# SilentStepStick-TMC2130_v10.net
KiCad netlist of a schematic drawn in EAGLE
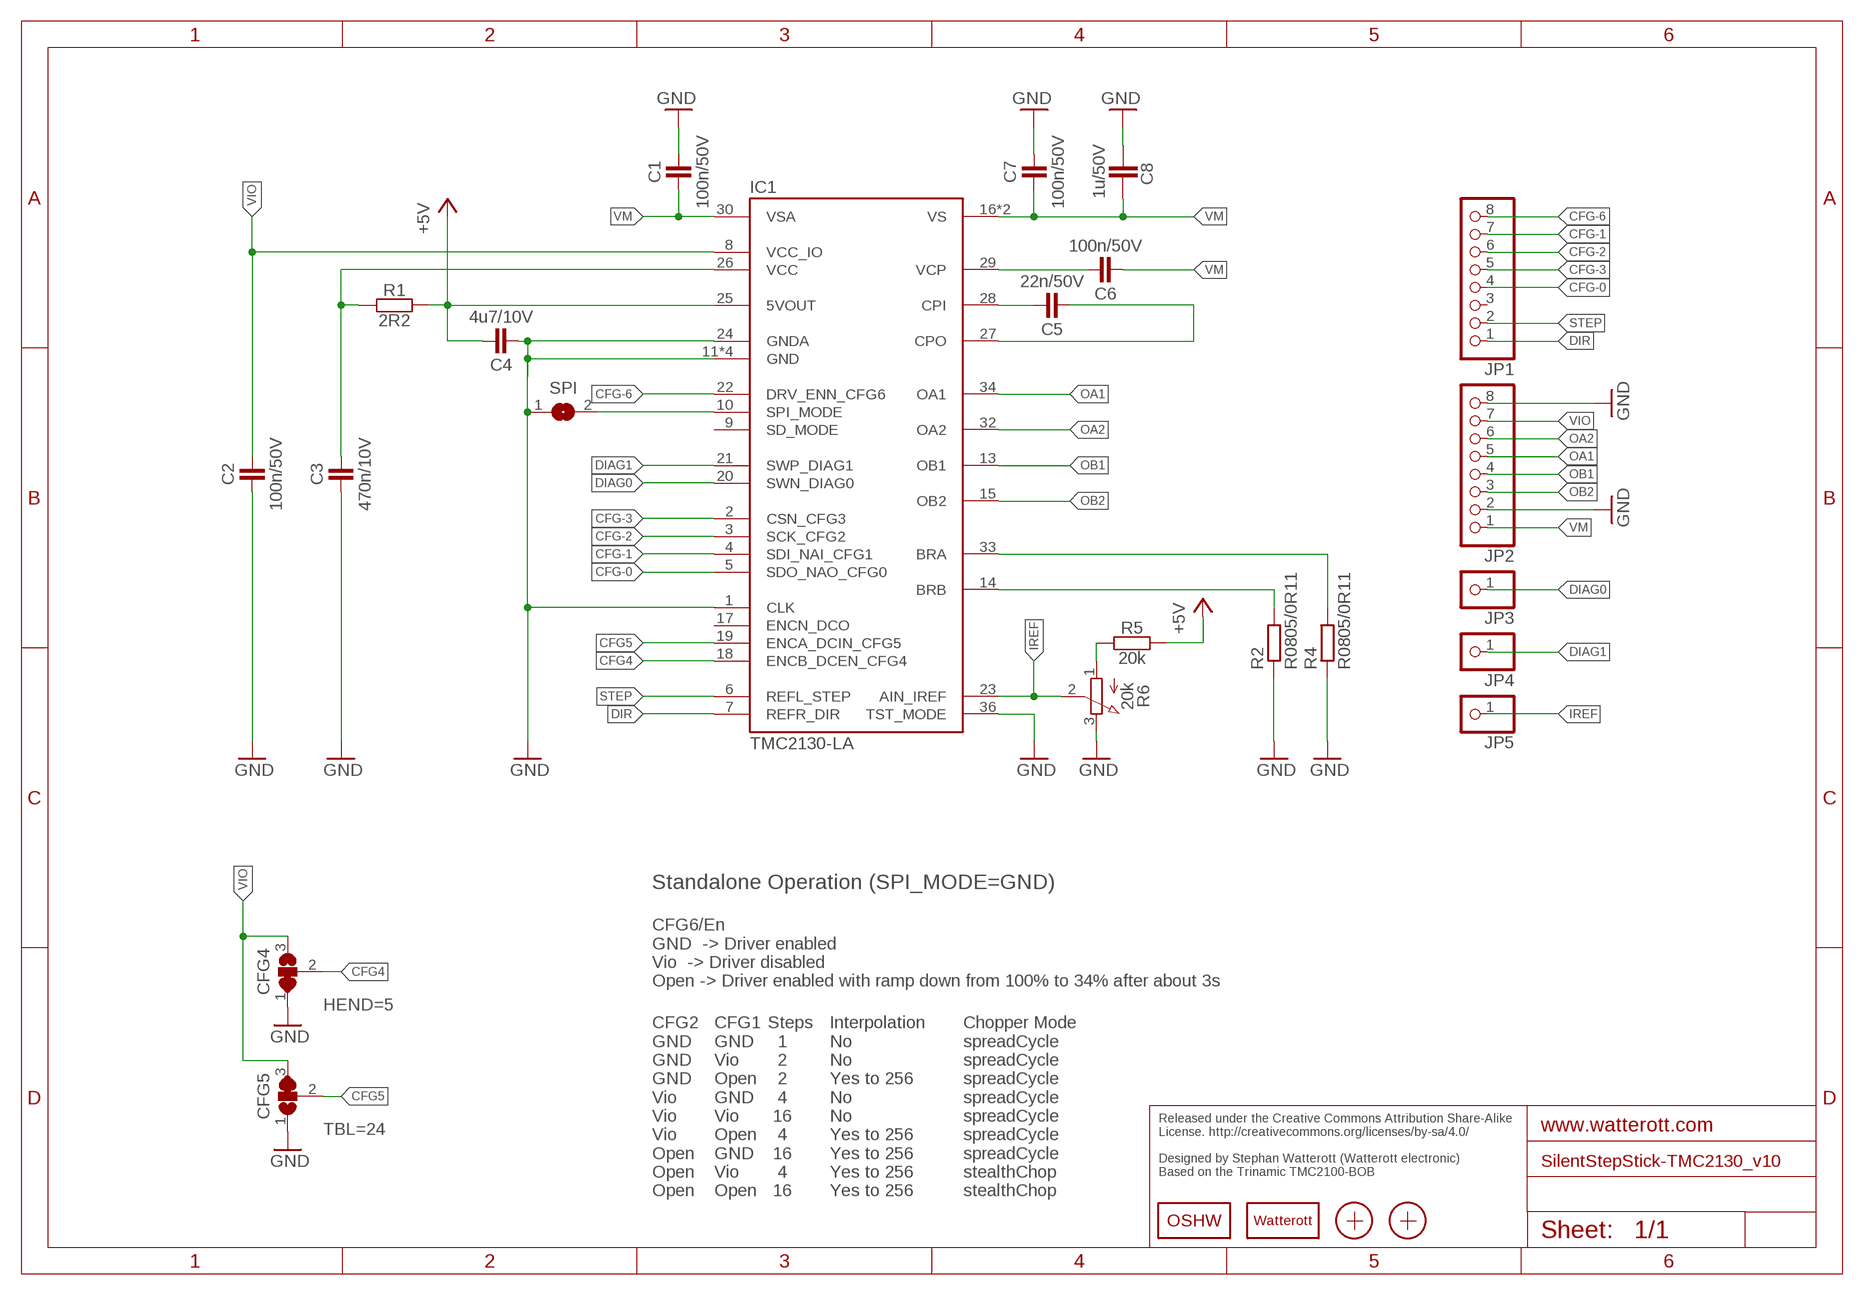
[diagram p0: schematic, sheet 1]

(export (version "E")
  (design (tool "Eeschema 10.0.6"))
  (components
    (comp (ref "C1")
      (value "100n/50V")
      (footprint "eagle-import:C0402")
      (libsource (lib "eagle-import") (part "CAPACITOR-0402"))
    )
    (comp (ref "C2")
      (value "100n/50V")
      (footprint "eagle-import:C0402")
      (libsource (lib "eagle-import") (part "CAPACITOR-0402"))
    )
    (comp (ref "C3")
      (value "470n/10V")
      (footprint "eagle-import:C0402")
      (libsource (lib "eagle-import") (part "CAPACITOR-0402"))
    )
    (comp (ref "C4")
      (value "4u7/10V")
      (footprint "eagle-import:C0402")
      (libsource (lib "eagle-import") (part "CAPACITOR-0402"))
    )
    (comp (ref "C5")
      (value "22n/50V")
      (footprint "eagle-import:C0402")
      (libsource (lib "eagle-import") (part "CAPACITOR-0402"))
    )
    (comp (ref "C6")
      (value "100n/50V")
      (footprint "eagle-import:C0402")
      (libsource (lib "eagle-import") (part "CAPACITOR-0402"))
    )
    (comp (ref "C7")
      (value "100n/50V")
      (footprint "eagle-import:C0402")
      (libsource (lib "eagle-import") (part "CAPACITOR-0402"))
    )
    (comp (ref "C8")
      (value "1u/50V")
      (footprint "eagle-import:C0603")
      (libsource (lib "eagle-import") (part "C-EUC0603"))
    )
    (comp (ref "CFG4")
      (value "JUMPER3-0201")
      (footprint "eagle-import:JUMPER3-0201")
      (libsource (lib "eagle-import") (part "JUMPER3-0201"))
    )
    (comp (ref "CFG5")
      (value "JUMPER3-0201")
      (footprint "eagle-import:JUMPER3-0201")
      (libsource (lib "eagle-import") (part "JUMPER3-0201"))
    )
    (comp (ref "IC1")
      (value "TMC2130-LA")
      (footprint "eagle-import:QFN36-PAD")
      (libsource (lib "eagle-import") (part "TMC21X0-LA"))
    )
    (comp (ref "JP1")
      (value "PINHD-1X08_2.54-S")
      (footprint "eagle-import:1X08-S")
      (libsource (lib "eagle-import") (part "PINHD-1X08_2.54-S"))
    )
    (comp (ref "JP2")
      (value "PINHD-1X08_2.54-S")
      (footprint "eagle-import:1X08-S")
      (libsource (lib "eagle-import") (part "PINHD-1X08_2.54-S"))
    )
    (comp (ref "JP3")
      (value "PINHD-1X1")
      (footprint "eagle-import:1X01")
      (libsource (lib "eagle-import") (part "PINHD-1X1"))
    )
    (comp (ref "JP4")
      (value "PINHD-1X1")
      (footprint "eagle-import:1X01")
      (libsource (lib "eagle-import") (part "PINHD-1X1"))
    )
    (comp (ref "JP5")
      (value "PINHD-1X1")
      (footprint "eagle-import:1X01")
      (libsource (lib "eagle-import") (part "PINHD-1X1"))
    )
    (comp (ref "LOGO1")
      (value "OSHW_LOGOX0070")
      (footprint "eagle-import:OSHW_6X70")
      (libsource (lib "eagle-import") (part "OSHW_LOGOX0070"))
    )
    (comp (ref "LOGO2")
      (value "LOGO-S_PLACE_M")
      (footprint "eagle-import:SPARK_TPLACE_M")
      (libsource (lib "eagle-import") (part "LOGO-S_PLACE_M"))
    )
    (comp (ref "R1")
      (value "2R2")
      (footprint "eagle-import:C0402")
      (libsource (lib "eagle-import") (part "RESISTOR-0402"))
    )
    (comp (ref "R2")
      (value "R0805/0R11")
      (footprint "eagle-import:M0805")
      (libsource (lib "eagle-import") (part "R-EU_M0805"))
    )
    (comp (ref "R4")
      (value "R0805/0R11")
      (footprint "eagle-import:M0805")
      (libsource (lib "eagle-import") (part "R-EU_M0805"))
    )
    (comp (ref "R5")
      (value "20k")
      (footprint "eagle-import:C0402")
      (libsource (lib "eagle-import") (part "RESISTOR-0402"))
    )
    (comp (ref "R6")
      (value "20k")
      (footprint "eagle-import:POT_EVM3R")
      (libsource (lib "eagle-import") (part "POTEVM3R"))
    )
    (comp (ref "SPI")
      (value "JUMPER2-0402-NC")
      (footprint "eagle-import:JUMPER2-0402_NC")
      (libsource (lib "eagle-import") (part "JUMPER2-0402-NC"))
    )
    (comp (ref "X1")
      (value "PASSER-07")
      (footprint "eagle-import:PASSER_07MM")
      (libsource (lib "eagle-import") (part "PASSER-07"))
    )
    (comp (ref "X2")
      (value "PASSER-07")
      (footprint "eagle-import:PASSER_07MM")
      (libsource (lib "eagle-import") (part "PASSER-07"))
    )
  )
  (nets
    (net (code "1") (name "+5V") (class "Default")
      (node (ref "C4") (pin "2") (pinfunction "2_2") (pintype "passive"))
      (node (ref "IC1") (pin "25") (pinfunction "5VOUT_25") (pintype "power_in"))
      (node (ref "R1") (pin "2") (pinfunction "2_2") (pintype "passive"))
      (node (ref "R5") (pin "2") (pinfunction "2_2") (pintype "passive"))
    )
    (net (code "2") (name "CFG-0") (class "Default")
      (node (ref "IC1") (pin "5") (pinfunction "SDO_NAO_CFG0_5") (pintype "bidirectional"))
      (node (ref "JP1") (pin "4") (pinfunction "4_4") (pintype "passive"))
    )
    (net (code "3") (name "CFG-1") (class "Default")
      (node (ref "IC1") (pin "4") (pinfunction "SDI_NAI_CFG1_4") (pintype "bidirectional"))
      (node (ref "JP1") (pin "7") (pinfunction "7_7") (pintype "passive"))
    )
    (net (code "4") (name "CFG-2") (class "Default")
      (node (ref "IC1") (pin "3") (pinfunction "SCK_CFG2_3") (pintype "bidirectional"))
      (node (ref "JP1") (pin "6") (pinfunction "6_6") (pintype "passive"))
    )
    (net (code "5") (name "CFG-3") (class "Default")
      (node (ref "IC1") (pin "2") (pinfunction "CSN_CFG3_2") (pintype "bidirectional"))
      (node (ref "JP1") (pin "5") (pinfunction "5_5") (pintype "passive"))
    )
    (net (code "6") (name "CFG-6") (class "Default")
      (node (ref "IC1") (pin "22") (pinfunction "DRV_ENN_CFG6_22") (pintype "bidirectional"))
      (node (ref "JP1") (pin "8") (pinfunction "8_8") (pintype "passive"))
    )
    (net (code "7") (name "CFG4") (class "Default")
      (node (ref "CFG4") (pin "2") (pinfunction "2_2") (pintype "passive"))
      (node (ref "IC1") (pin "18") (pinfunction "ENCB_DCEN_CFG4_18") (pintype "bidirectional"))
    )
    (net (code "8") (name "CFG5") (class "Default")
      (node (ref "CFG5") (pin "2") (pinfunction "2_2") (pintype "passive"))
      (node (ref "IC1") (pin "19") (pinfunction "ENCA_DCIN_CFG5_19") (pintype "bidirectional"))
    )
    (net (code "9") (name "DIAG0") (class "Default")
      (node (ref "IC1") (pin "20") (pinfunction "SWN_DIAG0_20") (pintype "bidirectional"))
      (node (ref "JP3") (pin "1") (pinfunction "1_1") (pintype "passive"))
    )
    (net (code "10") (name "DIAG1") (class "Default")
      (node (ref "IC1") (pin "21") (pinfunction "SWP_DIAG1_21") (pintype "bidirectional"))
      (node (ref "JP4") (pin "1") (pinfunction "1_1") (pintype "passive"))
    )
    (net (code "11") (name "DIR") (class "Default")
      (node (ref "IC1") (pin "7") (pinfunction "REFR_DIR_7") (pintype "bidirectional"))
      (node (ref "JP1") (pin "1") (pinfunction "1_1") (pintype "passive"))
    )
    (net (code "12") (name "GND") (class "Default")
      (node (ref "C1") (pin "2") (pinfunction "2_2") (pintype "passive"))
      (node (ref "C2") (pin "1") (pinfunction "1_1") (pintype "passive"))
      (node (ref "C3") (pin "1") (pinfunction "1_1") (pintype "passive"))
      (node (ref "C4") (pin "1") (pinfunction "1_1") (pintype "passive"))
      (node (ref "C7") (pin "2") (pinfunction "2_2") (pintype "passive"))
      (node (ref "C8") (pin "2") (pinfunction "2_2") (pintype "passive"))
      (node (ref "CFG4") (pin "1") (pinfunction "1_1") (pintype "passive"))
      (node (ref "CFG5") (pin "1") (pinfunction "1_1") (pintype "passive"))
      (node (ref "IC1") (pin "1") (pinfunction "CLK_1") (pintype "bidirectional"))
      (node (ref "IC1") (pin "11") (pinfunction "GND_11") (pintype "power_in"))
      (node (ref "IC1") (pin "12") (pinfunction "GND_12") (pintype "power_in"))
      (node (ref "IC1") (pin "24") (pinfunction "GNDA_24") (pintype "power_in"))
      (node (ref "IC1") (pin "35") (pinfunction "GND_35") (pintype "power_in"))
      (node (ref "IC1") (pin "36") (pinfunction "TST_MODE_36") (pintype "bidirectional"))
      (node (ref "IC1") (pin "TP") (pinfunction "GND_TP") (pintype "power_in"))
      (node (ref "JP2") (pin "2") (pinfunction "2_2") (pintype "passive"))
      (node (ref "JP2") (pin "8") (pinfunction "8_8") (pintype "passive"))
      (node (ref "R2") (pin "1") (pinfunction "1_1") (pintype "passive"))
      (node (ref "R4") (pin "1") (pinfunction "1_1") (pintype "passive"))
      (node (ref "R6") (pin "3") (pinfunction "E_3") (pintype "passive"))
      (node (ref "SPI") (pin "1") (pinfunction "1_1") (pintype "passive"))
    )
    (net (code "13") (name "IREF") (class "Default")
      (node (ref "IC1") (pin "23") (pinfunction "AIN_IREF_23") (pintype "passive"))
      (node (ref "JP5") (pin "1") (pinfunction "1_1") (pintype "passive"))
      (node (ref "R6") (pin "2") (pinfunction "S_2") (pintype "passive"))
    )
    (net (code "14") (name "Net-(IC1-BRA)") (class "Default")
      (node (ref "IC1") (pin "33") (pinfunction "BRA_33") (pintype "output"))
      (node (ref "R4") (pin "2") (pinfunction "2_2") (pintype "passive"))
    )
    (net (code "15") (name "Net-(IC1-BRB)") (class "Default")
      (node (ref "IC1") (pin "14") (pinfunction "BRB_14") (pintype "output"))
      (node (ref "R2") (pin "2") (pinfunction "2_2") (pintype "passive"))
    )
    (net (code "16") (name "Net-(IC1-CPI)") (class "Default")
      (node (ref "C5") (pin "2") (pinfunction "2_2") (pintype "passive"))
      (node (ref "IC1") (pin "28") (pinfunction "CPI_28") (pintype "passive"))
    )
    (net (code "17") (name "Net-(IC1-CPO)") (class "Default")
      (node (ref "C5") (pin "1") (pinfunction "1_1") (pintype "passive"))
      (node (ref "IC1") (pin "27") (pinfunction "CPO_27") (pintype "passive"))
    )
    (net (code "18") (name "Net-(IC1-SPI_MODE)") (class "Default")
      (node (ref "IC1") (pin "10") (pinfunction "SPI_MODE_10") (pintype "bidirectional"))
      (node (ref "SPI") (pin "2") (pinfunction "2_2") (pintype "passive"))
    )
    (net (code "19") (name "Net-(IC1-VCC)") (class "Default")
      (node (ref "C3") (pin "2") (pinfunction "2_2") (pintype "passive"))
      (node (ref "IC1") (pin "26") (pinfunction "VCC_26") (pintype "power_in"))
      (node (ref "R1") (pin "1") (pinfunction "1_1") (pintype "passive"))
    )
    (net (code "20") (name "Net-(IC1-VCP)") (class "Default")
      (node (ref "C6") (pin "2") (pinfunction "2_2") (pintype "passive"))
      (node (ref "IC1") (pin "29") (pinfunction "VCP_29") (pintype "passive"))
    )
    (net (code "21") (name "Net-(R6-A)") (class "Default")
      (node (ref "R5") (pin "1") (pinfunction "1_1") (pintype "passive"))
      (node (ref "R6") (pin "1") (pinfunction "A_1") (pintype "passive"))
    )
    (net (code "22") (name "OA1") (class "Default")
      (node (ref "IC1") (pin "34") (pinfunction "OA1_34") (pintype "output"))
      (node (ref "JP2") (pin "5") (pinfunction "5_5") (pintype "passive"))
    )
    (net (code "23") (name "OA2") (class "Default")
      (node (ref "IC1") (pin "32") (pinfunction "OA2_32") (pintype "output"))
      (node (ref "JP2") (pin "6") (pinfunction "6_6") (pintype "passive"))
    )
    (net (code "24") (name "OB1") (class "Default")
      (node (ref "IC1") (pin "13") (pinfunction "OB1_13") (pintype "output"))
      (node (ref "JP2") (pin "4") (pinfunction "4_4") (pintype "passive"))
    )
    (net (code "25") (name "OB2") (class "Default")
      (node (ref "IC1") (pin "15") (pinfunction "OB2_15") (pintype "output"))
      (node (ref "JP2") (pin "3") (pinfunction "3_3") (pintype "passive"))
    )
    (net (code "26") (name "STEP") (class "Default")
      (node (ref "IC1") (pin "6") (pinfunction "REFL_STEP_6") (pintype "bidirectional"))
      (node (ref "JP1") (pin "2") (pinfunction "2_2") (pintype "passive"))
    )
    (net (code "27") (name "VIO") (class "Default")
      (node (ref "C2") (pin "2") (pinfunction "2_2") (pintype "passive"))
      (node (ref "CFG4") (pin "3") (pinfunction "3_3") (pintype "passive"))
      (node (ref "CFG5") (pin "3") (pinfunction "3_3") (pintype "passive"))
      (node (ref "IC1") (pin "8") (pinfunction "VCC_IO_8") (pintype "power_in"))
      (node (ref "JP2") (pin "7") (pinfunction "7_7") (pintype "passive"))
    )
    (net (code "28") (name "VM") (class "Default")
      (node (ref "C1") (pin "1") (pinfunction "1_1") (pintype "passive"))
      (node (ref "C6") (pin "1") (pinfunction "1_1") (pintype "passive"))
      (node (ref "C7") (pin "1") (pinfunction "1_1") (pintype "passive"))
      (node (ref "C8") (pin "1") (pinfunction "1_1") (pintype "passive"))
      (node (ref "IC1") (pin "16") (pinfunction "VS_16") (pintype "power_in"))
      (node (ref "IC1") (pin "30") (pinfunction "VSA_30") (pintype "power_in"))
      (node (ref "IC1") (pin "31") (pinfunction "VS_31") (pintype "power_in"))
      (node (ref "JP2") (pin "1") (pinfunction "1_1") (pintype "passive"))
    )
    (net (code "29") (name "unconnected-(IC1-ENCN_DCO-Pad17)") (class "Default")
      (node (ref "IC1") (pin "17") (pinfunction "ENCN_DCO_17") (pintype "bidirectional"))
    )
    (net (code "30") (name "unconnected-(IC1-SD_MODE-Pad9)") (class "Default")
      (node (ref "IC1") (pin "9") (pinfunction "SD_MODE_9") (pintype "bidirectional"))
    )
    (net (code "31") (name "unconnected-(JP1-Pad3)") (class "Default")
      (node (ref "JP1") (pin "3") (pinfunction "3_3") (pintype "passive"))
    )
  )
)
